# true-bypass.net
KiCad netlist of a schematic drawn in EAGLE
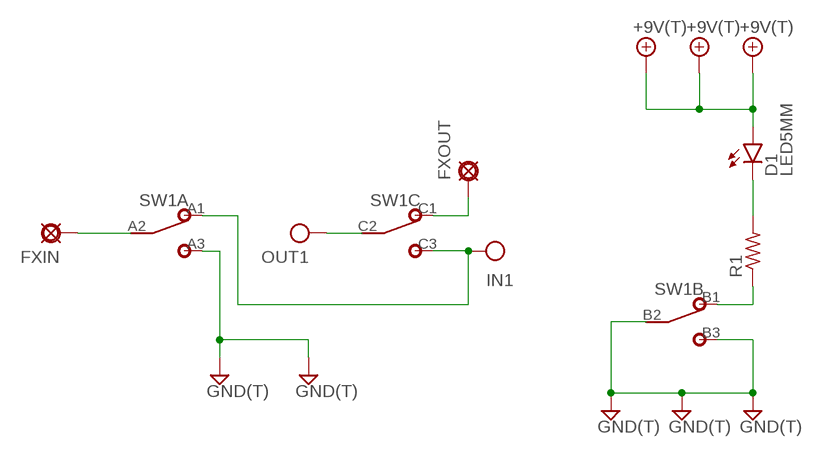
[diagram p0: schematic, sheet 1]

(export (version "E")
  (design (tool "Eeschema 10.0.6"))
  (components
    (comp (ref "+9V1")
      (value "+9V(T)")
      (footprint "eagle-import:SQUARE")
      (libsource (lib "eagle-import") (part "+9V(T)"))
    )
    (comp (ref "+9V2")
      (value "+9V(T)")
      (footprint "eagle-import:SQUARE")
      (libsource (lib "eagle-import") (part "+9V(T)"))
    )
    (comp (ref "+9V3")
      (value "+9V(T)")
      (footprint "eagle-import:SQUARE")
      (libsource (lib "eagle-import") (part "+9V(T)"))
    )
    (comp (ref "D1")
      (value "LED5MM")
      (footprint "eagle-import:LED5MM")
      (libsource (lib "eagle-import") (part "LED5MM"))
    )
    (comp (ref "FXIN")
      (value "PAD")
      (footprint "eagle-import:SQUARE")
      (libsource (lib "eagle-import") (part "PAD"))
    )
    (comp (ref "FXOUT")
      (value "PAD")
      (footprint "eagle-import:SQUARE")
      (libsource (lib "eagle-import") (part "PAD"))
    )
    (comp (ref "GND1")
      (value "GND(T)")
      (footprint "eagle-import:SQUARE")
      (libsource (lib "eagle-import") (part "GND(T)"))
    )
    (comp (ref "GND2")
      (value "GND(T)")
      (footprint "eagle-import:SQUARE")
      (libsource (lib "eagle-import") (part "GND(T)"))
    )
    (comp (ref "GND3")
      (value "GND(T)")
      (footprint "eagle-import:SQUARE")
      (libsource (lib "eagle-import") (part "GND(T)"))
    )
    (comp (ref "GND4")
      (value "GND(T)")
      (footprint "eagle-import:SQUARE")
      (libsource (lib "eagle-import") (part "GND(T)"))
    )
    (comp (ref "GND5")
      (value "GND(T)")
      (footprint "eagle-import:SQUARE")
      (libsource (lib "eagle-import") (part "GND(T)"))
    )
    (comp (ref "IN1")
      (value "IN(T)")
      (footprint "eagle-import:SQUARE")
      (libsource (lib "eagle-import") (part "IN(T)"))
    )
    (comp (ref "OUT1")
      (value "OUT(T)")
      (footprint "eagle-import:SQUARE")
      (libsource (lib "eagle-import") (part "OUT(T)"))
    )
    (comp (ref "R1")
      (value "6MM.3")
      (footprint "eagle-import:R0207_3")
      (libsource (lib "eagle-import") (part "6MM.3"))
    )
    (comp (ref "SW1")
      (value "3PDTBLUE")
      (footprint "eagle-import:CHINABLUE")
      (libsource (lib "eagle-import") (part "3PDTBLUE"))
    )
  )
  (nets
    (net (code "1") (name "+9V(T)") (class "Default")
      (node (ref "+9V1") (pin "1") (pinfunction "+9V_1") (pintype "power_in"))
      (node (ref "+9V2") (pin "1") (pinfunction "+9V_1") (pintype "power_in"))
      (node (ref "+9V3") (pin "1") (pinfunction "+9V_1") (pintype "power_in"))
      (node (ref "D1") (pin "A") (pinfunction "A_A") (pintype "passive"))
    )
    (net (code "2") (name "GND(T)") (class "Default")
      (node (ref "GND1") (pin "1") (pinfunction "GND_1") (pintype "power_in"))
      (node (ref "GND2") (pin "1") (pinfunction "GND_1") (pintype "power_in"))
      (node (ref "GND3") (pin "1") (pinfunction "GND_1") (pintype "power_in"))
      (node (ref "GND4") (pin "1") (pinfunction "GND_1") (pintype "power_in"))
      (node (ref "GND5") (pin "1") (pinfunction "GND_1") (pintype "power_in"))
      (node (ref "SW1") (pin "A3") (pinfunction "3_A3") (pintype "passive"))
      (node (ref "SW1") (pin "B2") (pinfunction "2_B2") (pintype "passive"))
      (node (ref "SW1") (pin "B3") (pinfunction "3_B3") (pintype "passive"))
    )
    (net (code "3") (name "IN(T)") (class "Default")
      (node (ref "IN1") (pin "1") (pinfunction "IN_1") (pintype "power_in"))
      (node (ref "SW1") (pin "A1") (pinfunction "1_A1") (pintype "passive"))
      (node (ref "SW1") (pin "C3") (pinfunction "3_C3") (pintype "passive"))
    )
    (net (code "4") (name "Net-(D1-C)") (class "Default")
      (node (ref "D1") (pin "K") (pinfunction "C_K") (pintype "passive"))
      (node (ref "R1") (pin "2") (pinfunction "2_2") (pintype "passive"))
    )
    (net (code "5") (name "Net-(FXIN-PAD)") (class "Default")
      (node (ref "FXIN") (pin "1") (pinfunction "PAD_1") (pintype "passive"))
      (node (ref "SW1") (pin "A2") (pinfunction "2_A2") (pintype "passive"))
    )
    (net (code "6") (name "Net-(FXOUT-PAD)") (class "Default")
      (node (ref "FXOUT") (pin "1") (pinfunction "PAD_1") (pintype "passive"))
      (node (ref "SW1") (pin "C1") (pinfunction "1_C1") (pintype "passive"))
    )
    (net (code "7") (name "Net-(SW1B-1)") (class "Default")
      (node (ref "R1") (pin "1") (pinfunction "1_1") (pintype "passive"))
      (node (ref "SW1") (pin "B1") (pinfunction "1_B1") (pintype "passive"))
    )
    (net (code "8") (name "OUT(T)") (class "Default")
      (node (ref "OUT1") (pin "1") (pinfunction "OUT_1") (pintype "power_in"))
      (node (ref "SW1") (pin "C2") (pinfunction "2_C2") (pintype "passive"))
    )
  )
)
